# CW342_Edge.net
KiCad netlist of a schematic drawn in Altium Designer
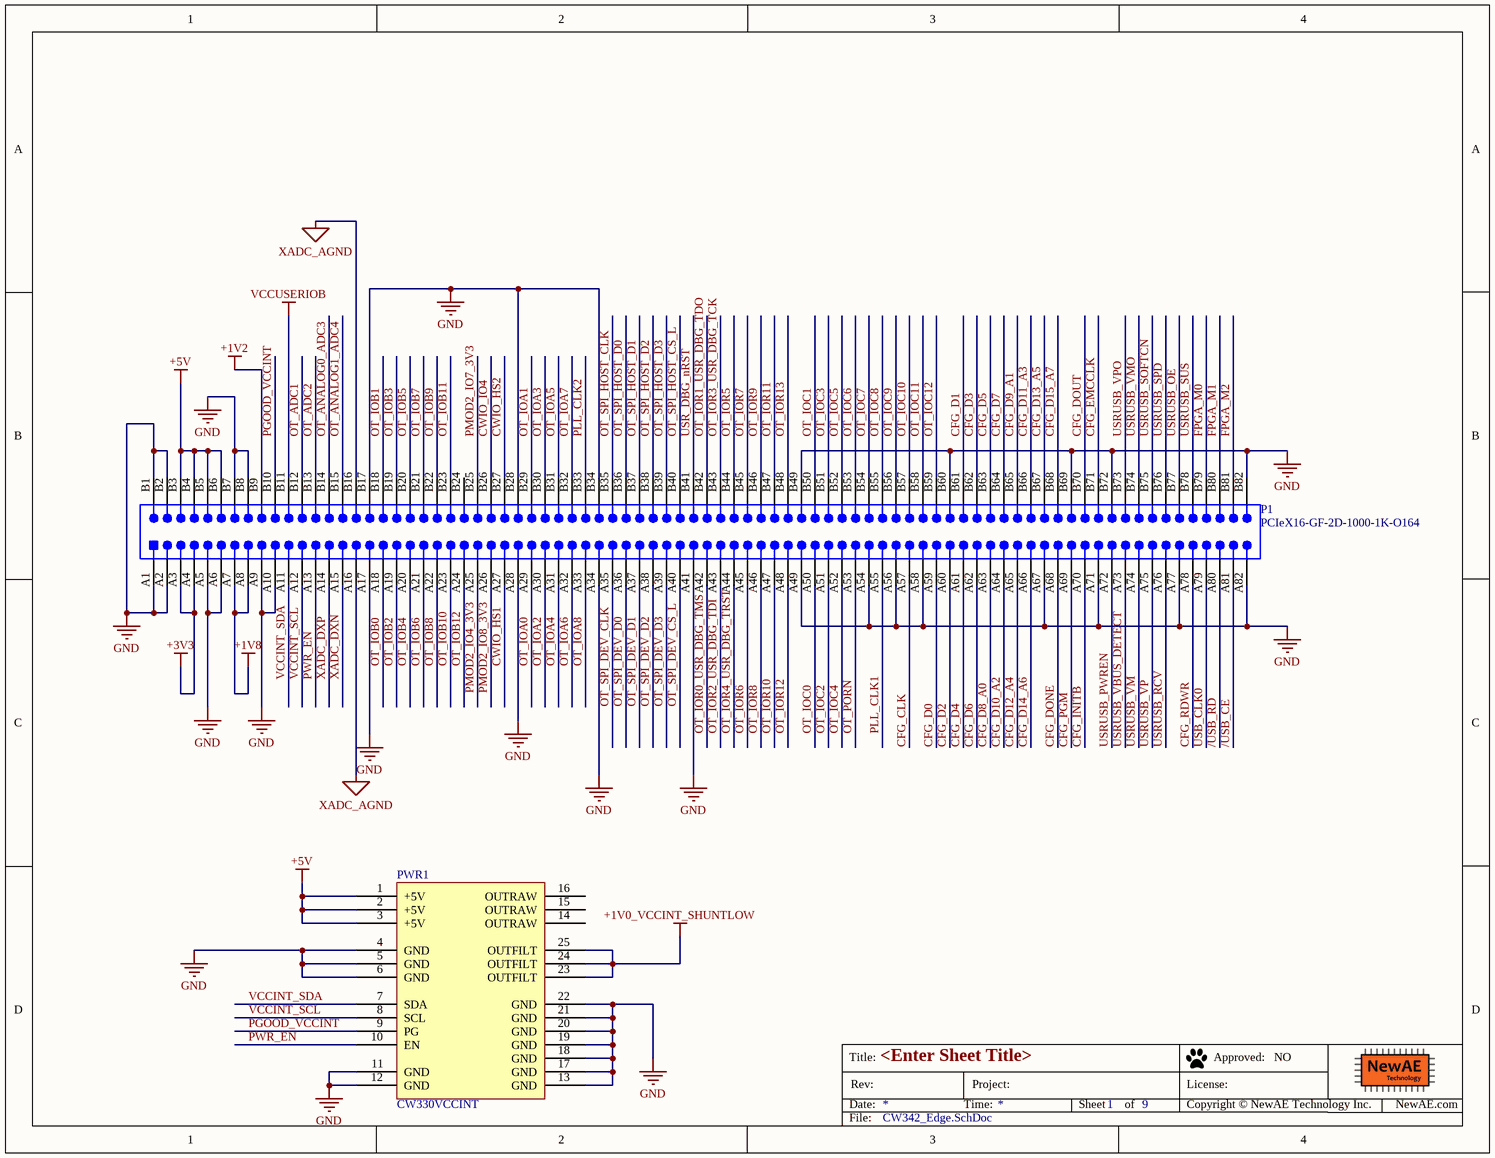
[diagram p0: CW342_Edge.SchDoc]

(export (version "E")
  (design (tool "Eeschema 10.0.6"))
  (components
    (comp (ref "P1")
      (value "PCIeX16-GF-2D-1000-1K-O164")
      (footprint "PCIeX16-GF-2D-1000-1K-O164")
      (description "Golden Finger, PCIeX16, Dual, Opposite, Pitch 1mm, 164-Position")
      (libsource (lib "NewAE Technology") (part "CN-2P-M-PCI164"))
    )
    (comp (ref "PWR1")
      (value "CW330VCCINT")
      (footprint "CW335_VCCINT_POWERSUPPLY")
      (libsource (lib "CW330_SubBoardLib") (part "CW330VCCINT"))
    )
  )
  (nets
    (net (code "1") (name "+1V0_VCCINT_SHUNTLOW") (class "Default")
      (node (ref "PWR1") (pin "23") (pinfunction "OUTFILT_23") (pintype "passive"))
      (node (ref "PWR1") (pin "24") (pinfunction "OUTFILT_24") (pintype "passive"))
      (node (ref "PWR1") (pin "25") (pinfunction "OUTFILT_25") (pintype "passive"))
    )
    (net (code "2") (name "+1V2") (class "Default")
      (node (ref "P1") (pin "B9") (pinfunction "B9_B9") (pintype "passive"))
    )
    (net (code "3") (name "+1V8") (class "Default")
      (node (ref "P1") (pin "A7") (pinfunction "A7_A7") (pintype "passive"))
      (node (ref "P1") (pin "A8") (pinfunction "A8_A8") (pintype "passive"))
    )
    (net (code "4") (name "+3V3") (class "Default")
      (node (ref "P1") (pin "A3") (pinfunction "A3_A3") (pintype "passive"))
      (node (ref "P1") (pin "A4") (pinfunction "A4_A4") (pintype "passive"))
    )
    (net (code "5") (name "+5V") (class "Default")
      (node (ref "P1") (pin "B3") (pinfunction "B3_B3") (pintype "passive"))
      (node (ref "P1") (pin "B4") (pinfunction "B4_B4") (pintype "passive"))
      (node (ref "P1") (pin "B5") (pinfunction "B5_B5") (pintype "passive"))
      (node (ref "P1") (pin "B6") (pinfunction "B6_B6") (pintype "passive"))
      (node (ref "PWR1") (pin "1") (pinfunction "+5V_1") (pintype "passive"))
      (node (ref "PWR1") (pin "2") (pinfunction "+5V_2") (pintype "passive"))
      (node (ref "PWR1") (pin "3") (pinfunction "+5V_3") (pintype "passive"))
    )
    (net (code "6") (name "/CFG_CLK") (class "Default")
      (node (ref "P1") (pin "A57") (pinfunction "A57_A57") (pintype "passive"))
    )
    (net (code "7") (name "/CFG_D0") (class "Default")
      (node (ref "P1") (pin "A59") (pinfunction "A59_A59") (pintype "passive"))
    )
    (net (code "8") (name "/CFG_D1") (class "Default")
      (node (ref "P1") (pin "B61") (pinfunction "B61_B61") (pintype "passive"))
    )
    (net (code "9") (name "/CFG_D2") (class "Default")
      (node (ref "P1") (pin "A60") (pinfunction "A60_A60") (pintype "passive"))
    )
    (net (code "10") (name "/CFG_D3") (class "Default")
      (node (ref "P1") (pin "B62") (pinfunction "B62_B62") (pintype "passive"))
    )
    (net (code "11") (name "/CFG_D4") (class "Default")
      (node (ref "P1") (pin "A61") (pinfunction "A61_A61") (pintype "passive"))
    )
    (net (code "12") (name "/CFG_D5") (class "Default")
      (node (ref "P1") (pin "B63") (pinfunction "B63_B63") (pintype "passive"))
    )
    (net (code "13") (name "/CFG_D6") (class "Default")
      (node (ref "P1") (pin "A62") (pinfunction "A62_A62") (pintype "passive"))
    )
    (net (code "14") (name "/CFG_D7") (class "Default")
      (node (ref "P1") (pin "B64") (pinfunction "B64_B64") (pintype "passive"))
    )
    (net (code "15") (name "/CFG_D8_A0") (class "Default")
      (node (ref "P1") (pin "A63") (pinfunction "A63_A63") (pintype "passive"))
    )
    (net (code "16") (name "/CFG_D9_A1") (class "Default")
      (node (ref "P1") (pin "B65") (pinfunction "B65_B65") (pintype "passive"))
    )
    (net (code "17") (name "/CFG_D10_A2") (class "Default")
      (node (ref "P1") (pin "A64") (pinfunction "A64_A64") (pintype "passive"))
    )
    (net (code "18") (name "/CFG_D11_A3") (class "Default")
      (node (ref "P1") (pin "B66") (pinfunction "B66_B66") (pintype "passive"))
    )
    (net (code "19") (name "/CFG_D12_A4") (class "Default")
      (node (ref "P1") (pin "A65") (pinfunction "A65_A65") (pintype "passive"))
    )
    (net (code "20") (name "/CFG_D13_A5") (class "Default")
      (node (ref "P1") (pin "B67") (pinfunction "B67_B67") (pintype "passive"))
    )
    (net (code "21") (name "/CFG_D14_A6") (class "Default")
      (node (ref "P1") (pin "A66") (pinfunction "A66_A66") (pintype "passive"))
    )
    (net (code "22") (name "/CFG_D15_A7") (class "Default")
      (node (ref "P1") (pin "B68") (pinfunction "B68_B68") (pintype "passive"))
    )
    (net (code "23") (name "/CFG_DONE") (class "Default")
      (node (ref "P1") (pin "A68") (pinfunction "A68_A68") (pintype "passive"))
    )
    (net (code "24") (name "/CFG_DOUT") (class "Default")
      (node (ref "P1") (pin "B70") (pinfunction "B70_B70") (pintype "passive"))
    )
    (net (code "25") (name "/CFG_EMCCLK") (class "Default")
      (node (ref "P1") (pin "B71") (pinfunction "B71_B71") (pintype "passive"))
    )
    (net (code "26") (name "/CFG_INITB") (class "Default")
      (node (ref "P1") (pin "A70") (pinfunction "A70_A70") (pintype "passive"))
    )
    (net (code "27") (name "/CFG_PGM") (class "Default")
      (node (ref "P1") (pin "A69") (pinfunction "A69_A69") (pintype "passive"))
    )
    (net (code "28") (name "/CFG_RDWR") (class "Default")
      (node (ref "P1") (pin "A78") (pinfunction "A78_A78") (pintype "passive"))
    )
    (net (code "29") (name "/CWIO_HS1") (class "Default")
      (node (ref "P1") (pin "A27") (pinfunction "A27_A27") (pintype "passive"))
    )
    (net (code "30") (name "/CWIO_HS2") (class "Default")
      (node (ref "P1") (pin "B27") (pinfunction "B27_B27") (pintype "passive"))
    )
    (net (code "31") (name "/CWIO_IO4") (class "Default")
      (node (ref "P1") (pin "B26") (pinfunction "B26_B26") (pintype "passive"))
    )
    (net (code "32") (name "/FPGA_M0") (class "Default")
      (node (ref "P1") (pin "B79") (pinfunction "B79_B79") (pintype "passive"))
    )
    (net (code "33") (name "/FPGA_M1") (class "Default")
      (node (ref "P1") (pin "B80") (pinfunction "B80_B80") (pintype "passive"))
    )
    (net (code "34") (name "/FPGA_M2") (class "Default")
      (node (ref "P1") (pin "B81") (pinfunction "B81_B81") (pintype "passive"))
    )
    (net (code "35") (name "/OT_ADC1") (class "Default")
      (node (ref "P1") (pin "B12") (pinfunction "B12_B12") (pintype "passive"))
    )
    (net (code "36") (name "/OT_ADC2") (class "Default")
      (node (ref "P1") (pin "B13") (pinfunction "B13_B13") (pintype "passive"))
    )
    (net (code "37") (name "/OT_ANALOG0_ADC3") (class "Default")
      (node (ref "P1") (pin "B14") (pinfunction "B14_B14") (pintype "passive"))
    )
    (net (code "38") (name "/OT_ANALOG1_ADC4") (class "Default")
      (node (ref "P1") (pin "B15") (pinfunction "B15_B15") (pintype "passive"))
    )
    (net (code "39") (name "/OT_IOA0") (class "Default")
      (node (ref "P1") (pin "A29") (pinfunction "A29_A29") (pintype "passive"))
    )
    (net (code "40") (name "/OT_IOA1") (class "Default")
      (node (ref "P1") (pin "B29") (pinfunction "B29_B29") (pintype "passive"))
    )
    (net (code "41") (name "/OT_IOA2") (class "Default")
      (node (ref "P1") (pin "A30") (pinfunction "A30_A30") (pintype "passive"))
    )
    (net (code "42") (name "/OT_IOA3") (class "Default")
      (node (ref "P1") (pin "B30") (pinfunction "B30_B30") (pintype "passive"))
    )
    (net (code "43") (name "/OT_IOA4") (class "Default")
      (node (ref "P1") (pin "A31") (pinfunction "A31_A31") (pintype "passive"))
    )
    (net (code "44") (name "/OT_IOA5") (class "Default")
      (node (ref "P1") (pin "B31") (pinfunction "B31_B31") (pintype "passive"))
    )
    (net (code "45") (name "/OT_IOA6") (class "Default")
      (node (ref "P1") (pin "A32") (pinfunction "A32_A32") (pintype "passive"))
    )
    (net (code "46") (name "/OT_IOA7") (class "Default")
      (node (ref "P1") (pin "B32") (pinfunction "B32_B32") (pintype "passive"))
    )
    (net (code "47") (name "/OT_IOA8") (class "Default")
      (node (ref "P1") (pin "A33") (pinfunction "A33_A33") (pintype "passive"))
    )
    (net (code "48") (name "/OT_IOB0") (class "Default")
      (node (ref "P1") (pin "A18") (pinfunction "A18_A18") (pintype "passive"))
    )
    (net (code "49") (name "/OT_IOB1") (class "Default")
      (node (ref "P1") (pin "B18") (pinfunction "B18_B18") (pintype "passive"))
    )
    (net (code "50") (name "/OT_IOB2") (class "Default")
      (node (ref "P1") (pin "A19") (pinfunction "A19_A19") (pintype "passive"))
    )
    (net (code "51") (name "/OT_IOB3") (class "Default")
      (node (ref "P1") (pin "B19") (pinfunction "B19_B19") (pintype "passive"))
    )
    (net (code "52") (name "/OT_IOB4") (class "Default")
      (node (ref "P1") (pin "A20") (pinfunction "A20_A20") (pintype "passive"))
    )
    (net (code "53") (name "/OT_IOB5") (class "Default")
      (node (ref "P1") (pin "B20") (pinfunction "B20_B20") (pintype "passive"))
    )
    (net (code "54") (name "/OT_IOB6") (class "Default")
      (node (ref "P1") (pin "A21") (pinfunction "A21_A21") (pintype "passive"))
    )
    (net (code "55") (name "/OT_IOB7") (class "Default")
      (node (ref "P1") (pin "B21") (pinfunction "B21_B21") (pintype "passive"))
    )
    (net (code "56") (name "/OT_IOB8") (class "Default")
      (node (ref "P1") (pin "A22") (pinfunction "A22_A22") (pintype "passive"))
    )
    (net (code "57") (name "/OT_IOB9") (class "Default")
      (node (ref "P1") (pin "B22") (pinfunction "B22_B22") (pintype "passive"))
    )
    (net (code "58") (name "/OT_IOB10") (class "Default")
      (node (ref "P1") (pin "A23") (pinfunction "A23_A23") (pintype "passive"))
    )
    (net (code "59") (name "/OT_IOB11") (class "Default")
      (node (ref "P1") (pin "B23") (pinfunction "B23_B23") (pintype "passive"))
    )
    (net (code "60") (name "/OT_IOB12") (class "Default")
      (node (ref "P1") (pin "A24") (pinfunction "A24_A24") (pintype "passive"))
    )
    (net (code "61") (name "/OT_IOC0") (class "Default")
      (node (ref "P1") (pin "A50") (pinfunction "A50_A50") (pintype "passive"))
    )
    (net (code "62") (name "/OT_IOC1") (class "Default")
      (node (ref "P1") (pin "B50") (pinfunction "B50_B50") (pintype "passive"))
    )
    (net (code "63") (name "/OT_IOC2") (class "Default")
      (node (ref "P1") (pin "A51") (pinfunction "A51_A51") (pintype "passive"))
    )
    (net (code "64") (name "/OT_IOC3") (class "Default")
      (node (ref "P1") (pin "B51") (pinfunction "B51_B51") (pintype "passive"))
    )
    (net (code "65") (name "/OT_IOC4") (class "Default")
      (node (ref "P1") (pin "A52") (pinfunction "A52_A52") (pintype "passive"))
    )
    (net (code "66") (name "/OT_IOC5") (class "Default")
      (node (ref "P1") (pin "B52") (pinfunction "B52_B52") (pintype "passive"))
    )
    (net (code "67") (name "/OT_IOC6") (class "Default")
      (node (ref "P1") (pin "B53") (pinfunction "B53_B53") (pintype "passive"))
    )
    (net (code "68") (name "/OT_IOC7") (class "Default")
      (node (ref "P1") (pin "B54") (pinfunction "B54_B54") (pintype "passive"))
    )
    (net (code "69") (name "/OT_IOC8") (class "Default")
      (node (ref "P1") (pin "B55") (pinfunction "B55_B55") (pintype "passive"))
    )
    (net (code "70") (name "/OT_IOC9") (class "Default")
      (node (ref "P1") (pin "B56") (pinfunction "B56_B56") (pintype "passive"))
    )
    (net (code "71") (name "/OT_IOC10") (class "Default")
      (node (ref "P1") (pin "B57") (pinfunction "B57_B57") (pintype "passive"))
    )
    (net (code "72") (name "/OT_IOC11") (class "Default")
      (node (ref "P1") (pin "B58") (pinfunction "B58_B58") (pintype "passive"))
    )
    (net (code "73") (name "/OT_IOC12") (class "Default")
      (node (ref "P1") (pin "B59") (pinfunction "B59_B59") (pintype "passive"))
    )
    (net (code "74") (name "/OT_IOR0_USR_DBG_TMS") (class "Default")
      (node (ref "P1") (pin "A42") (pinfunction "A42_A42") (pintype "passive"))
    )
    (net (code "75") (name "/OT_IOR1_USR_DBG_TDO") (class "Default")
      (node (ref "P1") (pin "B42") (pinfunction "B42_B42") (pintype "passive"))
    )
    (net (code "76") (name "/OT_IOR2_USR_DBG_TDI") (class "Default")
      (node (ref "P1") (pin "A43") (pinfunction "A43_A43") (pintype "passive"))
    )
    (net (code "77") (name "/OT_IOR3_USR_DBG_TCK") (class "Default")
      (node (ref "P1") (pin "B43") (pinfunction "B43_B43") (pintype "passive"))
    )
    (net (code "78") (name "/OT_IOR4_USR_DBG_TRST") (class "Default")
      (node (ref "P1") (pin "A44") (pinfunction "A44_A44") (pintype "passive"))
    )
    (net (code "79") (name "/OT_IOR5") (class "Default")
      (node (ref "P1") (pin "B44") (pinfunction "B44_B44") (pintype "passive"))
    )
    (net (code "80") (name "/OT_IOR6") (class "Default")
      (node (ref "P1") (pin "A45") (pinfunction "A45_A45") (pintype "passive"))
    )
    (net (code "81") (name "/OT_IOR7") (class "Default")
      (node (ref "P1") (pin "B45") (pinfunction "B45_B45") (pintype "passive"))
    )
    (net (code "82") (name "/OT_IOR8") (class "Default")
      (node (ref "P1") (pin "A46") (pinfunction "A46_A46") (pintype "passive"))
    )
    (net (code "83") (name "/OT_IOR9") (class "Default")
      (node (ref "P1") (pin "B46") (pinfunction "B46_B46") (pintype "passive"))
    )
    (net (code "84") (name "/OT_IOR10") (class "Default")
      (node (ref "P1") (pin "A47") (pinfunction "A47_A47") (pintype "passive"))
    )
    (net (code "85") (name "/OT_IOR11") (class "Default")
      (node (ref "P1") (pin "B47") (pinfunction "B47_B47") (pintype "passive"))
    )
    (net (code "86") (name "/OT_IOR12") (class "Default")
      (node (ref "P1") (pin "A48") (pinfunction "A48_A48") (pintype "passive"))
    )
    (net (code "87") (name "/OT_IOR13") (class "Default")
      (node (ref "P1") (pin "B48") (pinfunction "B48_B48") (pintype "passive"))
    )
    (net (code "88") (name "/OT_PORN") (class "Default")
      (node (ref "P1") (pin "A53") (pinfunction "A53_A53") (pintype "passive"))
    )
    (net (code "89") (name "/OT_SPI_DEV_CLK") (class "Default")
      (node (ref "P1") (pin "A35") (pinfunction "A35_A35") (pintype "passive"))
    )
    (net (code "90") (name "/OT_SPI_DEV_CS_L") (class "Default")
      (node (ref "P1") (pin "A40") (pinfunction "A40_A40") (pintype "passive"))
    )
    (net (code "91") (name "/OT_SPI_DEV_D0") (class "Default")
      (node (ref "P1") (pin "A36") (pinfunction "A36_A36") (pintype "passive"))
    )
    (net (code "92") (name "/OT_SPI_DEV_D1") (class "Default")
      (node (ref "P1") (pin "A37") (pinfunction "A37_A37") (pintype "passive"))
    )
    (net (code "93") (name "/OT_SPI_DEV_D2") (class "Default")
      (node (ref "P1") (pin "A38") (pinfunction "A38_A38") (pintype "passive"))
    )
    (net (code "94") (name "/OT_SPI_DEV_D3") (class "Default")
      (node (ref "P1") (pin "A39") (pinfunction "A39_A39") (pintype "passive"))
    )
    (net (code "95") (name "/OT_SPI_HOST_CLK") (class "Default")
      (node (ref "P1") (pin "B35") (pinfunction "B35_B35") (pintype "passive"))
    )
    (net (code "96") (name "/OT_SPI_HOST_CS_L") (class "Default")
      (node (ref "P1") (pin "B40") (pinfunction "B40_B40") (pintype "passive"))
    )
    (net (code "97") (name "/OT_SPI_HOST_D0") (class "Default")
      (node (ref "P1") (pin "B36") (pinfunction "B36_B36") (pintype "passive"))
    )
    (net (code "98") (name "/OT_SPI_HOST_D1") (class "Default")
      (node (ref "P1") (pin "B37") (pinfunction "B37_B37") (pintype "passive"))
    )
    (net (code "99") (name "/OT_SPI_HOST_D2") (class "Default")
      (node (ref "P1") (pin "B38") (pinfunction "B38_B38") (pintype "passive"))
    )
    (net (code "100") (name "/OT_SPI_HOST_D3") (class "Default")
      (node (ref "P1") (pin "B39") (pinfunction "B39_B39") (pintype "passive"))
    )
    (net (code "101") (name "/PGOOD_VCCINT") (class "Default")
      (node (ref "P1") (pin "B10") (pinfunction "B10_B10") (pintype "passive"))
      (node (ref "PWR1") (pin "9") (pinfunction "PG_9") (pintype "passive"))
    )
    (net (code "102") (name "/PLL_CLK1") (class "Default")
      (node (ref "P1") (pin "A55") (pinfunction "A55_A55") (pintype "passive"))
    )
    (net (code "103") (name "/PLL_CLK2") (class "Default")
      (node (ref "P1") (pin "B33") (pinfunction "B33_B33") (pintype "passive"))
    )
    (net (code "104") (name "/PMOD2_IO4_3V3") (class "Default")
      (node (ref "P1") (pin "A25") (pinfunction "A25_A25") (pintype "passive"))
    )
    (net (code "105") (name "/PMOD2_IO7_3V3") (class "Default")
      (node (ref "P1") (pin "B25") (pinfunction "B25_B25") (pintype "passive"))
    )
    (net (code "106") (name "/PMOD2_IO8_3V3") (class "Default")
      (node (ref "P1") (pin "A26") (pinfunction "A26_A26") (pintype "passive"))
    )
    (net (code "107") (name "/PWR_EN") (class "Default")
      (node (ref "P1") (pin "A13") (pinfunction "A13_A13") (pintype "passive"))
      (node (ref "PWR1") (pin "10") (pinfunction "EN_10") (pintype "passive"))
    )
    (net (code "108") (name "/USB_CLK0") (class "Default")
      (node (ref "P1") (pin "A79") (pinfunction "A79_A79") (pintype "passive"))
    )
    (net (code "109") (name "/USRUSB_OE") (class "Default")
      (node (ref "P1") (pin "B77") (pinfunction "B77_B77") (pintype "passive"))
    )
    (net (code "110") (name "/USRUSB_PWREN") (class "Default")
      (node (ref "P1") (pin "A72") (pinfunction "A72_A72") (pintype "passive"))
    )
    (net (code "111") (name "/USRUSB_RCV") (class "Default")
      (node (ref "P1") (pin "A76") (pinfunction "A76_A76") (pintype "passive"))
    )
    (net (code "112") (name "/USRUSB_SOFTCN") (class "Default")
      (node (ref "P1") (pin "B75") (pinfunction "B75_B75") (pintype "passive"))
    )
    (net (code "113") (name "/USRUSB_SPD") (class "Default")
      (node (ref "P1") (pin "B76") (pinfunction "B76_B76") (pintype "passive"))
    )
    (net (code "114") (name "/USRUSB_SUS") (class "Default")
      (node (ref "P1") (pin "B78") (pinfunction "B78_B78") (pintype "passive"))
    )
    (net (code "115") (name "/USRUSB_VBUS_DETECT") (class "Default")
      (node (ref "P1") (pin "A73") (pinfunction "A73_A73") (pintype "passive"))
    )
    (net (code "116") (name "/USRUSB_VM") (class "Default")
      (node (ref "P1") (pin "A74") (pinfunction "A74_A74") (pintype "passive"))
    )
    (net (code "117") (name "/USRUSB_VMO") (class "Default")
      (node (ref "P1") (pin "B74") (pinfunction "B74_B74") (pintype "passive"))
    )
    (net (code "118") (name "/USRUSB_VP") (class "Default")
      (node (ref "P1") (pin "A75") (pinfunction "A75_A75") (pintype "passive"))
    )
    (net (code "119") (name "/USRUSB_VPO") (class "Default")
      (node (ref "P1") (pin "B73") (pinfunction "B73_B73") (pintype "passive"))
    )
    (net (code "120") (name "/USR_DBG_nRST") (class "Default")
      (node (ref "P1") (pin "B41") (pinfunction "B41_B41") (pintype "passive"))
    )
    (net (code "121") (name "/VCCINT_SCL") (class "Default")
      (node (ref "P1") (pin "A12") (pinfunction "A12_A12") (pintype "passive"))
      (node (ref "PWR1") (pin "8") (pinfunction "SCL_8") (pintype "passive"))
    )
    (net (code "122") (name "/VCCINT_SDA") (class "Default")
      (node (ref "P1") (pin "A11") (pinfunction "A11_A11") (pintype "passive"))
      (node (ref "PWR1") (pin "7") (pinfunction "SDA_7") (pintype "passive"))
    )
    (net (code "123") (name "/XADC_DXN") (class "Default")
      (node (ref "P1") (pin "A15") (pinfunction "A15_A15") (pintype "passive"))
    )
    (net (code "124") (name "/XADC_DXP") (class "Default")
      (node (ref "P1") (pin "A14") (pinfunction "A14_A14") (pintype "passive"))
    )
    (net (code "125") (name "/{slash}USB_CE") (class "Default")
      (node (ref "P1") (pin "A81") (pinfunction "A81_A81") (pintype "passive"))
    )
    (net (code "126") (name "/{slash}USB_RD") (class "Default")
      (node (ref "P1") (pin "A80") (pinfunction "A80_A80") (pintype "passive"))
    )
    (net (code "127") (name "GND") (class "Default")
      (node (ref "P1") (pin "A1") (pinfunction "A1_A1") (pintype "passive"))
      (node (ref "P1") (pin "A10") (pinfunction "A10_A10") (pintype "passive"))
      (node (ref "P1") (pin "A17") (pinfunction "A17_A17") (pintype "passive"))
      (node (ref "P1") (pin "A2") (pinfunction "A2_A2") (pintype "passive"))
      (node (ref "P1") (pin "A28") (pinfunction "A28_A28") (pintype "passive"))
      (node (ref "P1") (pin "A34") (pinfunction "A34_A34") (pintype "passive"))
      (node (ref "P1") (pin "A41") (pinfunction "A41_A41") (pintype "passive"))
      (node (ref "P1") (pin "A49") (pinfunction "A49_A49") (pintype "passive"))
      (node (ref "P1") (pin "A5") (pinfunction "A5_A5") (pintype "passive"))
      (node (ref "P1") (pin "A54") (pinfunction "A54_A54") (pintype "passive"))
      (node (ref "P1") (pin "A56") (pinfunction "A56_A56") (pintype "passive"))
      (node (ref "P1") (pin "A58") (pinfunction "A58_A58") (pintype "passive"))
      (node (ref "P1") (pin "A6") (pinfunction "A6_A6") (pintype "passive"))
      (node (ref "P1") (pin "A67") (pinfunction "A67_A67") (pintype "passive"))
      (node (ref "P1") (pin "A71") (pinfunction "A71_A71") (pintype "passive"))
      (node (ref "P1") (pin "A77") (pinfunction "A77_A77") (pintype "passive"))
      (node (ref "P1") (pin "A82") (pinfunction "A82_A82") (pintype "passive"))
      (node (ref "P1") (pin "A9") (pinfunction "A9_A9") (pintype "passive"))
      (node (ref "P1") (pin "B1") (pinfunction "B1_B1") (pintype "passive"))
      (node (ref "P1") (pin "B17") (pinfunction "B17_B17") (pintype "passive"))
      (node (ref "P1") (pin "B2") (pinfunction "B2_B2") (pintype "passive"))
      (node (ref "P1") (pin "B28") (pinfunction "B28_B28") (pintype "passive"))
      (node (ref "P1") (pin "B34") (pinfunction "B34_B34") (pintype "passive"))
      (node (ref "P1") (pin "B49") (pinfunction "B49_B49") (pintype "passive"))
      (node (ref "P1") (pin "B60") (pinfunction "B60_B60") (pintype "passive"))
      (node (ref "P1") (pin "B69") (pinfunction "B69_B69") (pintype "passive"))
      (node (ref "P1") (pin "B7") (pinfunction "B7_B7") (pintype "passive"))
      (node (ref "P1") (pin "B72") (pinfunction "B72_B72") (pintype "passive"))
      (node (ref "P1") (pin "B8") (pinfunction "B8_B8") (pintype "passive"))
      (node (ref "P1") (pin "B82") (pinfunction "B82_B82") (pintype "passive"))
      (node (ref "PWR1") (pin "11") (pinfunction "GND_11") (pintype "passive"))
      (node (ref "PWR1") (pin "12") (pinfunction "GND_12") (pintype "passive"))
      (node (ref "PWR1") (pin "13") (pinfunction "GND_13") (pintype "passive"))
      (node (ref "PWR1") (pin "17") (pinfunction "GND_17") (pintype "passive"))
      (node (ref "PWR1") (pin "18") (pinfunction "GND_18") (pintype "passive"))
      (node (ref "PWR1") (pin "19") (pinfunction "GND_19") (pintype "passive"))
      (node (ref "PWR1") (pin "20") (pinfunction "GND_20") (pintype "passive"))
      (node (ref "PWR1") (pin "21") (pinfunction "GND_21") (pintype "passive"))
      (node (ref "PWR1") (pin "22") (pinfunction "GND_22") (pintype "passive"))
      (node (ref "PWR1") (pin "4") (pinfunction "GND_4") (pintype "passive"))
      (node (ref "PWR1") (pin "5") (pinfunction "GND_5") (pintype "passive"))
      (node (ref "PWR1") (pin "6") (pinfunction "GND_6") (pintype "passive"))
    )
    (net (code "128") (name "VCCUSERIOB") (class "Default")
      (node (ref "P1") (pin "B11") (pinfunction "B11_B11") (pintype "passive"))
    )
    (net (code "129") (name "XADC_AGND") (class "Default")
      (node (ref "P1") (pin "A16") (pinfunction "A16_A16") (pintype "passive"))
      (node (ref "P1") (pin "B16") (pinfunction "B16_B16") (pintype "passive"))
    )
    (net (code "130") (name "unconnected-(P1-PadB24)") (class "Default")
      (node (ref "P1") (pin "B24") (pinfunction "B24_B24") (pintype "passive"))
    )
    (net (code "131") (name "unconnected-(PWR1-OUTRAW-Pad14)") (class "Default")
      (node (ref "PWR1") (pin "14") (pinfunction "OUTRAW_14") (pintype "passive"))
    )
    (net (code "132") (name "unconnected-(PWR1-OUTRAW-Pad15)") (class "Default")
      (node (ref "PWR1") (pin "15") (pinfunction "OUTRAW_15") (pintype "passive"))
    )
    (net (code "133") (name "unconnected-(PWR1-OUTRAW-Pad16)") (class "Default")
      (node (ref "PWR1") (pin "16") (pinfunction "OUTRAW_16") (pintype "passive"))
    )
  )
)
